# OSSM-M5-Remote_v1.net
KiCad netlist of a schematic drawn in EAGLE
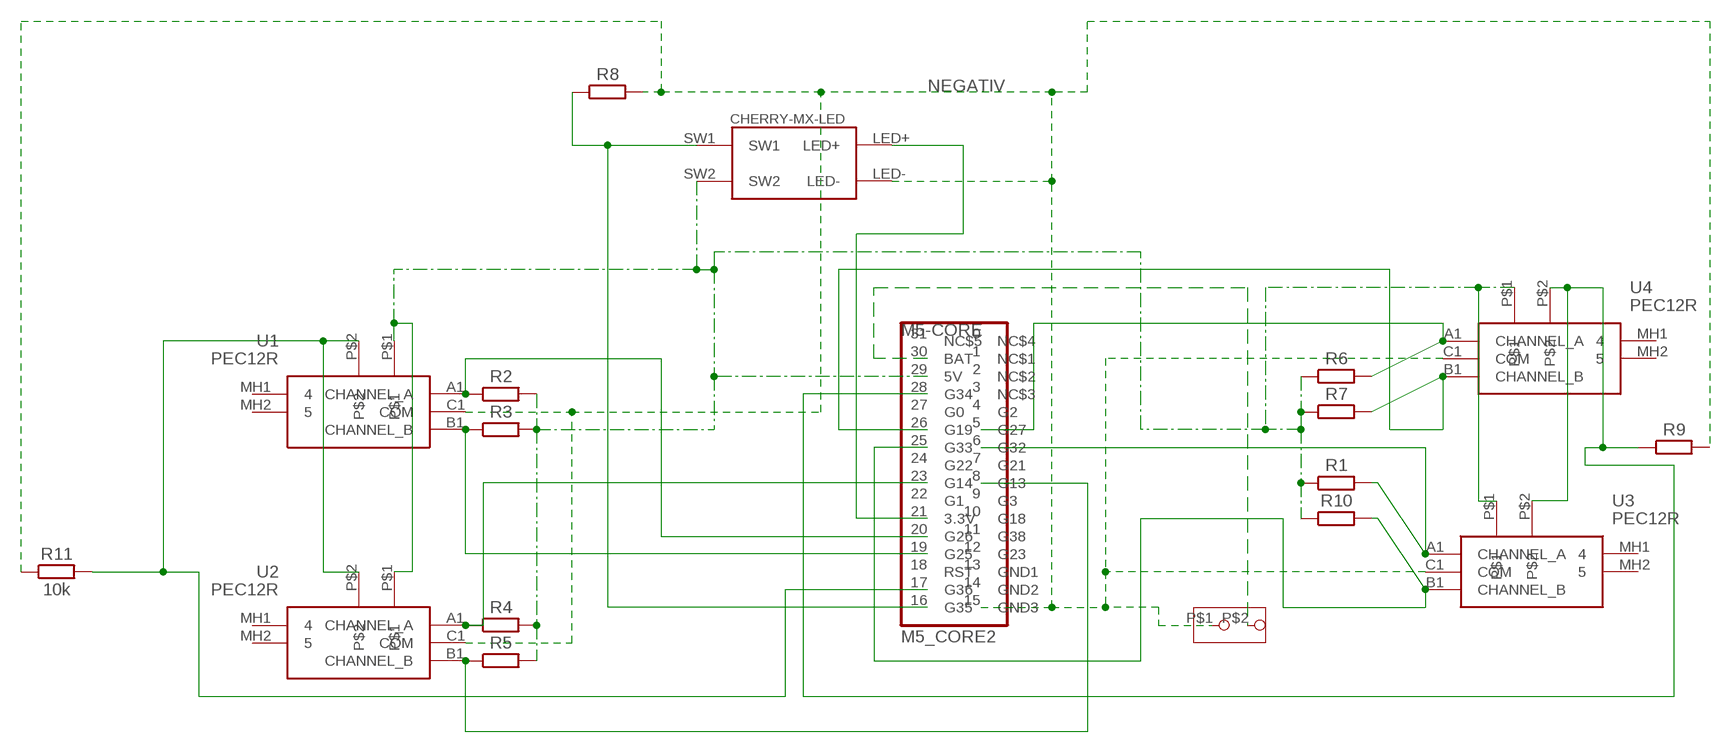
[diagram p0: schematic, sheet 1]

(export (version "E")
  (design (tool "Eeschema 10.0.6"))
  (components
    (comp (ref "M5-CORE")
      (value "M5_CORE2")
      (footprint "eagle-import:M5_CORE2")
      (libsource (lib "eagle-import") (part "M5_CORE2"))
    )
    (comp (ref "R1")
      (value "R_CHIP-1206(3216-METRIC)")
      (footprint "eagle-import:RESC3216X70")
      (libsource (lib "eagle-import") (part "RCHIP-1206(3216-METRIC)_"))
    )
    (comp (ref "R2")
      (value "R_CHIP-1206(3216-METRIC)")
      (footprint "eagle-import:RESC3216X70")
      (libsource (lib "eagle-import") (part "RCHIP-1206(3216-METRIC)_"))
    )
    (comp (ref "R3")
      (value "R_CHIP-1206(3216-METRIC)")
      (footprint "eagle-import:RESC3216X70")
      (libsource (lib "eagle-import") (part "RCHIP-1206(3216-METRIC)_"))
    )
    (comp (ref "R4")
      (value "R_CHIP-1206(3216-METRIC)")
      (footprint "eagle-import:RESC3216X70")
      (libsource (lib "eagle-import") (part "RCHIP-1206(3216-METRIC)_"))
    )
    (comp (ref "R5")
      (value "R_CHIP-1206(3216-METRIC)")
      (footprint "eagle-import:RESC3216X70")
      (libsource (lib "eagle-import") (part "RCHIP-1206(3216-METRIC)_"))
    )
    (comp (ref "R6")
      (value "R_CHIP-1206(3216-METRIC)")
      (footprint "eagle-import:RESC3216X70")
      (libsource (lib "eagle-import") (part "RCHIP-1206(3216-METRIC)_"))
    )
    (comp (ref "R7")
      (value "R_CHIP-1206(3216-METRIC)")
      (footprint "eagle-import:RESC3216X70")
      (libsource (lib "eagle-import") (part "RCHIP-1206(3216-METRIC)_"))
    )
    (comp (ref "R8")
      (value "R_CHIP-1206(3216-METRIC)")
      (footprint "eagle-import:RESC3216X70")
      (libsource (lib "eagle-import") (part "RCHIP-1206(3216-METRIC)_"))
    )
    (comp (ref "R9")
      (value "R_CHIP-1206(3216-METRIC)")
      (footprint "eagle-import:RESC3216X70")
      (libsource (lib "eagle-import") (part "RCHIP-1206(3216-METRIC)_"))
    )
    (comp (ref "R10")
      (value "R_CHIP-1206(3216-METRIC)")
      (footprint "eagle-import:RESC3216X70")
      (libsource (lib "eagle-import") (part "RCHIP-1206(3216-METRIC)_"))
    )
    (comp (ref "R11")
      (value "10k")
      (footprint "eagle-import:RESC3216X70")
      (libsource (lib "eagle-import") (part "RCHIP-1206(3216-METRIC)_"))
    )
    (comp (ref "U$3")
      (value "JST-PH-2MM,180")
      (footprint "eagle-import:JST-PH-2.0MM_180DEGREES")
      (libsource (lib "eagle-import") (part "JST-PH-2MM,180"))
    )
    (comp (ref "U$4")
      (value "CHERRY-MX-LED")
      (footprint "eagle-import:CHERRY-MX-LED")
      (libsource (lib "eagle-import") (part "CHERRY-MX-LED"))
    )
    (comp (ref "U1")
      (value "PEC12R")
      (footprint "eagle-import:PEC12R4017FN0024")
      (fields
        (field (name "ARROW_PART_NUMBER") "PEC12R-4230F-N0024")
        (field (name "MOUSER_PART_NUMBER") "652-PEC12R-4230F-N24")
      )
      (libsource (lib "eagle-import") (part "PEC12R-4230F-N0024"))
    )
    (comp (ref "U2")
      (value "PEC12R")
      (footprint "eagle-import:PEC12R4017FN0024")
      (fields
        (field (name "ARROW_PART_NUMBER") "PEC12R-4230F-N0024")
        (field (name "MOUSER_PART_NUMBER") "652-PEC12R-4230F-N24")
      )
      (libsource (lib "eagle-import") (part "PEC12R-4230F-N0024"))
    )
    (comp (ref "U3")
      (value "PEC12R")
      (footprint "eagle-import:PEC12R4017FN0024")
      (fields
        (field (name "ARROW_PART_NUMBER") "PEC12R-4230F-N0024")
        (field (name "MOUSER_PART_NUMBER") "652-PEC12R-4230F-N24")
      )
      (libsource (lib "eagle-import") (part "PEC12R-4230F-N0024"))
    )
    (comp (ref "U4")
      (value "PEC12R")
      (footprint "eagle-import:PEC12R4017FN0024")
      (fields
        (field (name "ARROW_PART_NUMBER") "PEC12R-4230F-N0024")
        (field (name "MOUSER_PART_NUMBER") "652-PEC12R-4230F-N24")
      )
      (libsource (lib "eagle-import") (part "PEC12R-4230F-N0024"))
    )
  )
  (nets
    (net (code "1") (name "/NEGATIV") (class "Default")
      (node (ref "M5-CORE") (pin "15") (pinfunction "GND3_15") (pintype "bidirectional"))
      (node (ref "R11") (pin "1") (pinfunction "1_1") (pintype "passive"))
      (node (ref "R8") (pin "2") (pinfunction "2_2") (pintype "passive"))
      (node (ref "R9") (pin "2") (pinfunction "2_2") (pintype "passive"))
      (node (ref "U$3") (pin "P$1") (pinfunction "P$1_P$1") (pintype "bidirectional"))
      (node (ref "U$4") (pin "LED-") (pinfunction "LED-_LED-") (pintype "bidirectional"))
      (node (ref "U1") (pin "C1") (pinfunction "COM_C1") (pintype "bidirectional"))
      (node (ref "U2") (pin "C1") (pinfunction "COM_C1") (pintype "bidirectional"))
      (node (ref "U3") (pin "C1") (pinfunction "COM_C1") (pintype "bidirectional"))
      (node (ref "U4") (pin "C1") (pinfunction "COM_C1") (pintype "bidirectional"))
    )
    (net (code "2") (name "Net-(M5-CORE-3.3V)") (class "Default")
      (node (ref "M5-CORE") (pin "21") (pinfunction "3.3V_21") (pintype "bidirectional"))
      (node (ref "U$4") (pin "LED+") (pinfunction "LED+_LED+") (pintype "bidirectional"))
    )
    (net (code "3") (name "Net-(M5-CORE-5V)") (class "Default")
      (node (ref "M5-CORE") (pin "29") (pinfunction "5V_29") (pintype "bidirectional"))
      (node (ref "R1") (pin "1") (pinfunction "1_1") (pintype "passive"))
      (node (ref "R10") (pin "1") (pinfunction "1_1") (pintype "passive"))
      (node (ref "R2") (pin "2") (pinfunction "2_2") (pintype "passive"))
      (node (ref "R3") (pin "2") (pinfunction "2_2") (pintype "passive"))
      (node (ref "R4") (pin "2") (pinfunction "2_2") (pintype "passive"))
      (node (ref "R5") (pin "2") (pinfunction "2_2") (pintype "passive"))
      (node (ref "R6") (pin "1") (pinfunction "1_1") (pintype "passive"))
      (node (ref "R7") (pin "1") (pinfunction "1_1") (pintype "passive"))
      (node (ref "U$4") (pin "SW2") (pinfunction "SW2_SW2") (pintype "bidirectional"))
      (node (ref "U1") (pin "P$1") (pinfunction "P$1_P$1") (pintype "bidirectional"))
      (node (ref "U2") (pin "P$1") (pinfunction "P$1_P$1") (pintype "bidirectional"))
      (node (ref "U3") (pin "P$1") (pinfunction "P$1_P$1") (pintype "bidirectional"))
      (node (ref "U4") (pin "P$1") (pinfunction "P$1_P$1") (pintype "bidirectional"))
    )
    (net (code "4") (name "Net-(M5-CORE-BAT)") (class "Default")
      (node (ref "M5-CORE") (pin "30") (pinfunction "BAT_30") (pintype "bidirectional"))
      (node (ref "U$3") (pin "P$2") (pinfunction "P$2_P$2") (pintype "bidirectional"))
    )
    (net (code "5") (name "Net-(M5-CORE-G13)") (class "Default")
      (node (ref "M5-CORE") (pin "8") (pinfunction "G13_8") (pintype "bidirectional"))
      (node (ref "R5") (pin "1") (pinfunction "1_1") (pintype "passive"))
      (node (ref "U2") (pin "B1") (pinfunction "CHANNEL_B_B1") (pintype "bidirectional"))
    )
    (net (code "6") (name "Net-(M5-CORE-G14)") (class "Default")
      (node (ref "M5-CORE") (pin "23") (pinfunction "G14_23") (pintype "bidirectional"))
      (node (ref "R4") (pin "1") (pinfunction "1_1") (pintype "passive"))
      (node (ref "U2") (pin "A1") (pinfunction "CHANNEL_A_A1") (pintype "bidirectional"))
    )
    (net (code "7") (name "Net-(M5-CORE-G19)") (class "Default")
      (node (ref "M5-CORE") (pin "26") (pinfunction "G19_26") (pintype "bidirectional"))
      (node (ref "R7") (pin "2") (pinfunction "2_2") (pintype "passive"))
      (node (ref "U4") (pin "B1") (pinfunction "CHANNEL_B_B1") (pintype "bidirectional"))
    )
    (net (code "8") (name "Net-(M5-CORE-G25)") (class "Default")
      (node (ref "M5-CORE") (pin "19") (pinfunction "G25_19") (pintype "bidirectional"))
      (node (ref "R3") (pin "1") (pinfunction "1_1") (pintype "passive"))
      (node (ref "U1") (pin "B1") (pinfunction "CHANNEL_B_B1") (pintype "bidirectional"))
    )
    (net (code "9") (name "Net-(M5-CORE-G26)") (class "Default")
      (node (ref "M5-CORE") (pin "20") (pinfunction "G26_20") (pintype "bidirectional"))
      (node (ref "R2") (pin "1") (pinfunction "1_1") (pintype "passive"))
      (node (ref "U1") (pin "A1") (pinfunction "CHANNEL_A_A1") (pintype "bidirectional"))
    )
    (net (code "10") (name "Net-(M5-CORE-G27)") (class "Default")
      (node (ref "M5-CORE") (pin "5") (pinfunction "G27_5") (pintype "bidirectional"))
      (node (ref "R6") (pin "2") (pinfunction "2_2") (pintype "passive"))
      (node (ref "U4") (pin "A1") (pinfunction "CHANNEL_A_A1") (pintype "bidirectional"))
    )
    (net (code "11") (name "Net-(M5-CORE-G32)") (class "Default")
      (node (ref "M5-CORE") (pin "6") (pinfunction "G32_6") (pintype "bidirectional"))
      (node (ref "R1") (pin "2") (pinfunction "2_2") (pintype "passive"))
      (node (ref "U3") (pin "A1") (pinfunction "CHANNEL_A_A1") (pintype "bidirectional"))
    )
    (net (code "12") (name "Net-(M5-CORE-G33)") (class "Default")
      (node (ref "M5-CORE") (pin "25") (pinfunction "G33_25") (pintype "bidirectional"))
      (node (ref "R10") (pin "2") (pinfunction "2_2") (pintype "passive"))
      (node (ref "U3") (pin "B1") (pinfunction "CHANNEL_B_B1") (pintype "bidirectional"))
    )
    (net (code "13") (name "Net-(M5-CORE-G34)") (class "Default")
      (node (ref "M5-CORE") (pin "28") (pinfunction "G34_28") (pintype "bidirectional"))
      (node (ref "R9") (pin "1") (pinfunction "1_1") (pintype "passive"))
      (node (ref "U3") (pin "P$2") (pinfunction "P$2_P$2") (pintype "bidirectional"))
      (node (ref "U4") (pin "P$2") (pinfunction "P$2_P$2") (pintype "bidirectional"))
    )
    (net (code "14") (name "Net-(M5-CORE-G35)") (class "Default")
      (node (ref "M5-CORE") (pin "16") (pinfunction "G35_16") (pintype "bidirectional"))
      (node (ref "R8") (pin "1") (pinfunction "1_1") (pintype "passive"))
      (node (ref "U$4") (pin "SW1") (pinfunction "SW1_SW1") (pintype "bidirectional"))
    )
    (net (code "15") (name "Net-(M5-CORE-G36)") (class "Default")
      (node (ref "M5-CORE") (pin "17") (pinfunction "G36_17") (pintype "bidirectional"))
      (node (ref "R11") (pin "2") (pinfunction "2_2") (pintype "passive"))
      (node (ref "U1") (pin "P$2") (pinfunction "P$2_P$2") (pintype "bidirectional"))
      (node (ref "U2") (pin "P$2") (pinfunction "P$2_P$2") (pintype "bidirectional"))
    )
    (net (code "16") (name "unconnected-(M5-CORE-G0-Pad27)") (class "Default")
      (node (ref "M5-CORE") (pin "27") (pinfunction "G0_27") (pintype "bidirectional"))
    )
    (net (code "17") (name "unconnected-(M5-CORE-G1-Pad22)") (class "Default")
      (node (ref "M5-CORE") (pin "22") (pinfunction "G1_22") (pintype "bidirectional"))
    )
    (net (code "18") (name "unconnected-(M5-CORE-G2-Pad4)") (class "Default")
      (node (ref "M5-CORE") (pin "4") (pinfunction "G2_4") (pintype "bidirectional"))
    )
    (net (code "19") (name "unconnected-(M5-CORE-G3-Pad9)") (class "Default")
      (node (ref "M5-CORE") (pin "9") (pinfunction "G3_9") (pintype "bidirectional"))
    )
    (net (code "20") (name "unconnected-(M5-CORE-G18-Pad10)") (class "Default")
      (node (ref "M5-CORE") (pin "10") (pinfunction "G18_10") (pintype "bidirectional"))
    )
    (net (code "21") (name "unconnected-(M5-CORE-G21-Pad7)") (class "Default")
      (node (ref "M5-CORE") (pin "7") (pinfunction "G21_7") (pintype "bidirectional"))
    )
    (net (code "22") (name "unconnected-(M5-CORE-G22-Pad24)") (class "Default")
      (node (ref "M5-CORE") (pin "24") (pinfunction "G22_24") (pintype "bidirectional"))
    )
    (net (code "23") (name "unconnected-(M5-CORE-G23-Pad12)") (class "Default")
      (node (ref "M5-CORE") (pin "12") (pinfunction "G23_12") (pintype "bidirectional"))
    )
    (net (code "24") (name "unconnected-(M5-CORE-G38-Pad11)") (class "Default")
      (node (ref "M5-CORE") (pin "11") (pinfunction "G38_11") (pintype "bidirectional"))
    )
    (net (code "25") (name "unconnected-(M5-CORE-GND1-Pad13)") (class "Default")
      (node (ref "M5-CORE") (pin "13") (pinfunction "GND1_13") (pintype "bidirectional"))
    )
    (net (code "26") (name "unconnected-(M5-CORE-GND2-Pad14)") (class "Default")
      (node (ref "M5-CORE") (pin "14") (pinfunction "GND2_14") (pintype "bidirectional"))
    )
    (net (code "27") (name "unconnected-(M5-CORE-NC$1-Pad1)") (class "Default")
      (node (ref "M5-CORE") (pin "1") (pinfunction "NC$1_1") (pintype "bidirectional"))
    )
    (net (code "28") (name "unconnected-(M5-CORE-NC$2-Pad2)") (class "Default")
      (node (ref "M5-CORE") (pin "2") (pinfunction "NC$2_2") (pintype "bidirectional"))
    )
    (net (code "29") (name "unconnected-(M5-CORE-NC$3-Pad3)") (class "Default")
      (node (ref "M5-CORE") (pin "3") (pinfunction "NC$3_3") (pintype "bidirectional"))
    )
    (net (code "30") (name "unconnected-(M5-CORE-NC$4-Pad0)") (class "Default")
      (node (ref "M5-CORE") (pin "0") (pinfunction "NC$4_0") (pintype "bidirectional"))
    )
    (net (code "31") (name "unconnected-(M5-CORE-NC$5-Pad31)") (class "Default")
      (node (ref "M5-CORE") (pin "31") (pinfunction "NC$5_31") (pintype "bidirectional"))
    )
    (net (code "32") (name "unconnected-(M5-CORE-RST-Pad18)") (class "Default")
      (node (ref "M5-CORE") (pin "18") (pinfunction "RST_18") (pintype "bidirectional"))
    )
    (net (code "33") (name "unconnected-(U1-4-PadMH1)") (class "Default")
      (node (ref "U1") (pin "MH1") (pinfunction "4_MH1") (pintype "bidirectional"))
    )
    (net (code "34") (name "unconnected-(U1-5-PadMH2)") (class "Default")
      (node (ref "U1") (pin "MH2") (pinfunction "5_MH2") (pintype "bidirectional"))
    )
    (net (code "35") (name "unconnected-(U2-4-PadMH1)") (class "Default")
      (node (ref "U2") (pin "MH1") (pinfunction "4_MH1") (pintype "bidirectional"))
    )
    (net (code "36") (name "unconnected-(U2-5-PadMH2)") (class "Default")
      (node (ref "U2") (pin "MH2") (pinfunction "5_MH2") (pintype "bidirectional"))
    )
    (net (code "37") (name "unconnected-(U3-4-PadMH1)") (class "Default")
      (node (ref "U3") (pin "MH1") (pinfunction "4_MH1") (pintype "bidirectional"))
    )
    (net (code "38") (name "unconnected-(U3-5-PadMH2)") (class "Default")
      (node (ref "U3") (pin "MH2") (pinfunction "5_MH2") (pintype "bidirectional"))
    )
    (net (code "39") (name "unconnected-(U4-4-PadMH1)") (class "Default")
      (node (ref "U4") (pin "MH1") (pinfunction "4_MH1") (pintype "bidirectional"))
    )
    (net (code "40") (name "unconnected-(U4-5-PadMH2)") (class "Default")
      (node (ref "U4") (pin "MH2") (pinfunction "5_MH2") (pintype "bidirectional"))
    )
  )
)
